# LED-controller-3.net
KiCad netlist of a schematic drawn in EAGLE
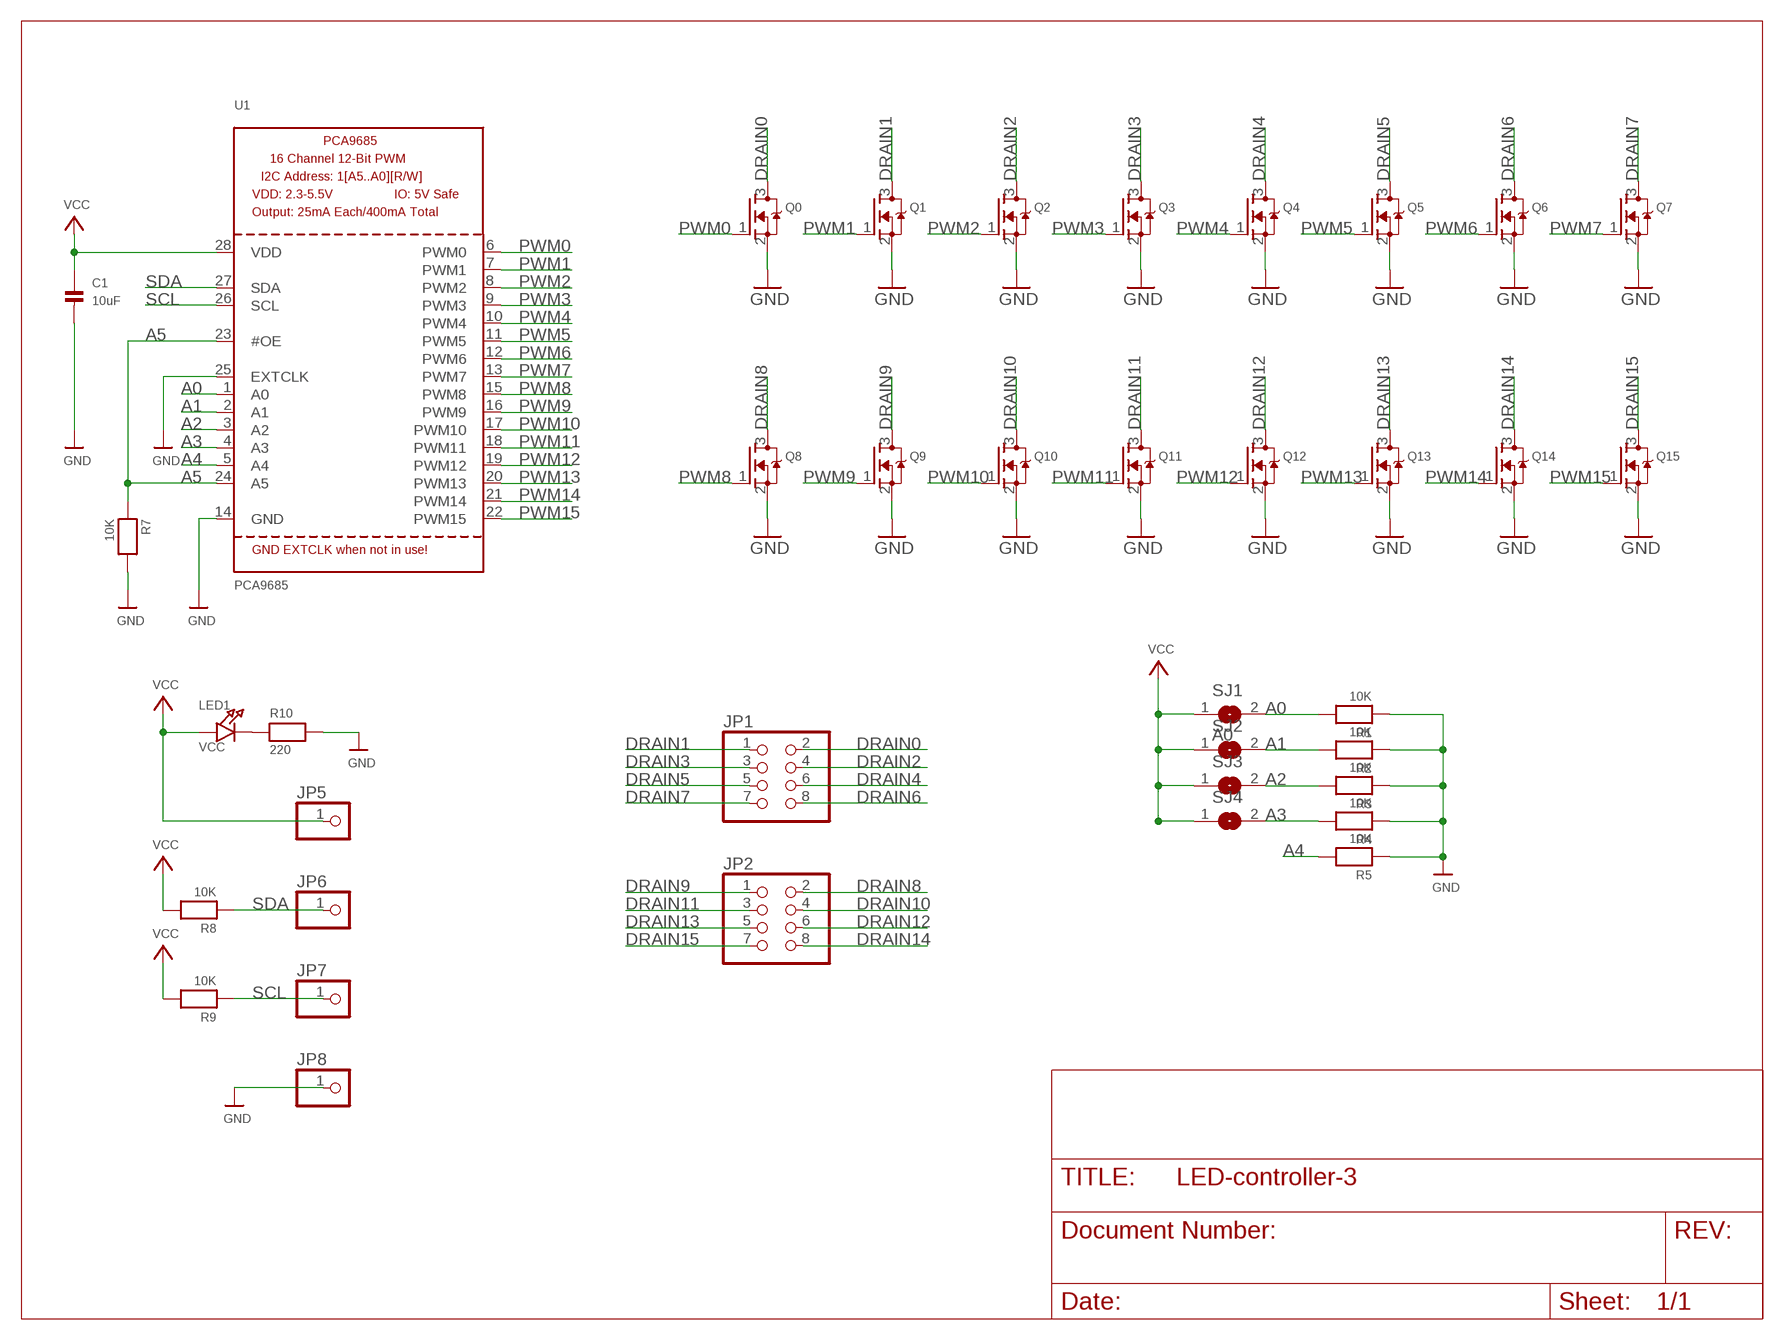
[diagram p0: schematic, sheet 1]

(export (version "E")
  (design (tool "Eeschema 10.0.6"))
  (components
    (comp (ref "C1")
      (value "10uF")
      (footprint "eagle-import:0805")
      (libsource (lib "eagle-import") (part "CAP_CERAMIC0805"))
    )
    (comp (ref "JP1")
      (value "PINHD-2X4")
      (footprint "eagle-import:2X04")
      (libsource (lib "eagle-import") (part "PINHD-2X4"))
    )
    (comp (ref "JP2")
      (value "PINHD-2X4")
      (footprint "eagle-import:2X04")
      (libsource (lib "eagle-import") (part "PINHD-2X4"))
    )
    (comp (ref "JP5")
      (value "PINHD-1X1CB")
      (footprint "eagle-import:1X01-CLEANBIG")
      (libsource (lib "eagle-import") (part "PINHD-1X1CB"))
    )
    (comp (ref "JP6")
      (value "PINHD-1X1CB")
      (footprint "eagle-import:1X01-CLEANBIG")
      (libsource (lib "eagle-import") (part "PINHD-1X1CB"))
    )
    (comp (ref "JP7")
      (value "PINHD-1X1CB")
      (footprint "eagle-import:1X01-CLEANBIG")
      (libsource (lib "eagle-import") (part "PINHD-1X1CB"))
    )
    (comp (ref "JP8")
      (value "PINHD-1X1CB")
      (footprint "eagle-import:1X01-CLEANBIG")
      (libsource (lib "eagle-import") (part "PINHD-1X1CB"))
    )
    (comp (ref "LED1")
      (value "VCC")
      (footprint "eagle-import:CHIPLED_0805")
      (libsource (lib "eagle-import") (part "LED0805"))
    )
    (comp (ref "Q0")
      (value "MOSFET-NREFLOW")
      (footprint "eagle-import:SOT23")
      (libsource (lib "eagle-import") (part "MOSFET-NREFLOW"))
    )
    (comp (ref "Q1")
      (value "MOSFET-NREFLOW")
      (footprint "eagle-import:SOT23")
      (libsource (lib "eagle-import") (part "MOSFET-NREFLOW"))
    )
    (comp (ref "Q2")
      (value "MOSFET-NREFLOW")
      (footprint "eagle-import:SOT23")
      (libsource (lib "eagle-import") (part "MOSFET-NREFLOW"))
    )
    (comp (ref "Q3")
      (value "MOSFET-NREFLOW")
      (footprint "eagle-import:SOT23")
      (libsource (lib "eagle-import") (part "MOSFET-NREFLOW"))
    )
    (comp (ref "Q4")
      (value "MOSFET-NREFLOW")
      (footprint "eagle-import:SOT23")
      (libsource (lib "eagle-import") (part "MOSFET-NREFLOW"))
    )
    (comp (ref "Q5")
      (value "MOSFET-NREFLOW")
      (footprint "eagle-import:SOT23")
      (libsource (lib "eagle-import") (part "MOSFET-NREFLOW"))
    )
    (comp (ref "Q6")
      (value "MOSFET-NREFLOW")
      (footprint "eagle-import:SOT23")
      (libsource (lib "eagle-import") (part "MOSFET-NREFLOW"))
    )
    (comp (ref "Q7")
      (value "MOSFET-NREFLOW")
      (footprint "eagle-import:SOT23")
      (libsource (lib "eagle-import") (part "MOSFET-NREFLOW"))
    )
    (comp (ref "Q8")
      (value "MOSFET-NREFLOW")
      (footprint "eagle-import:SOT23")
      (libsource (lib "eagle-import") (part "MOSFET-NREFLOW"))
    )
    (comp (ref "Q9")
      (value "MOSFET-NREFLOW")
      (footprint "eagle-import:SOT23")
      (libsource (lib "eagle-import") (part "MOSFET-NREFLOW"))
    )
    (comp (ref "Q10")
      (value "MOSFET-NREFLOW")
      (footprint "eagle-import:SOT23")
      (libsource (lib "eagle-import") (part "MOSFET-NREFLOW"))
    )
    (comp (ref "Q11")
      (value "MOSFET-NREFLOW")
      (footprint "eagle-import:SOT23")
      (libsource (lib "eagle-import") (part "MOSFET-NREFLOW"))
    )
    (comp (ref "Q12")
      (value "MOSFET-NREFLOW")
      (footprint "eagle-import:SOT23")
      (libsource (lib "eagle-import") (part "MOSFET-NREFLOW"))
    )
    (comp (ref "Q13")
      (value "MOSFET-NREFLOW")
      (footprint "eagle-import:SOT23")
      (libsource (lib "eagle-import") (part "MOSFET-NREFLOW"))
    )
    (comp (ref "Q14")
      (value "MOSFET-NREFLOW")
      (footprint "eagle-import:SOT23")
      (libsource (lib "eagle-import") (part "MOSFET-NREFLOW"))
    )
    (comp (ref "Q15")
      (value "MOSFET-NREFLOW")
      (footprint "eagle-import:SOT23")
      (libsource (lib "eagle-import") (part "MOSFET-NREFLOW"))
    )
    (comp (ref "R1")
      (value "10K")
      (footprint "eagle-import:0603")
      (libsource (lib "eagle-import") (part "RESISTOR0603"))
    )
    (comp (ref "R2")
      (value "10K")
      (footprint "eagle-import:0603")
      (libsource (lib "eagle-import") (part "RESISTOR0603"))
    )
    (comp (ref "R3")
      (value "10K")
      (footprint "eagle-import:0603")
      (libsource (lib "eagle-import") (part "RESISTOR0603"))
    )
    (comp (ref "R4")
      (value "10K")
      (footprint "eagle-import:0603")
      (libsource (lib "eagle-import") (part "RESISTOR0603"))
    )
    (comp (ref "R5")
      (value "10K")
      (footprint "eagle-import:0603")
      (libsource (lib "eagle-import") (part "RESISTOR0603"))
    )
    (comp (ref "R7")
      (value "10K")
      (footprint "eagle-import:0603")
      (libsource (lib "eagle-import") (part "RESISTOR0603"))
    )
    (comp (ref "R8")
      (value "10K")
      (footprint "eagle-import:0603")
      (libsource (lib "eagle-import") (part "RESISTOR0603"))
    )
    (comp (ref "R9")
      (value "10K")
      (footprint "eagle-import:0603")
      (libsource (lib "eagle-import") (part "RESISTOR0603"))
    )
    (comp (ref "R10")
      (value "220")
      (footprint "eagle-import:0603")
      (libsource (lib "eagle-import") (part "RESISTOR0603"))
    )
    (comp (ref "SJ1") (value "A0") (footprint "eagle-import:SJ") (libsource (lib "eagle-import") (part "SJ")))
    (comp (ref "SJ2") (value "SJ") (footprint "eagle-import:SJ") (libsource (lib "eagle-import") (part "SJ")))
    (comp (ref "SJ3") (value "SJ") (footprint "eagle-import:SJ") (libsource (lib "eagle-import") (part "SJ")))
    (comp (ref "SJ4") (value "SJ") (footprint "eagle-import:SJ") (libsource (lib "eagle-import") (part "SJ")))
    (comp (ref "U1")
      (value "PCA9685")
      (footprint "eagle-import:TSSOP28")
      (libsource (lib "eagle-import") (part "PCA9685"))
    )
  )
  (nets
    (net (code "1") (name "/A0") (class "Default")
      (node (ref "R1") (pin "2") (pinfunction "2_2") (pintype "passive"))
      (node (ref "SJ1") (pin "2") (pinfunction "2_2") (pintype "passive"))
      (node (ref "U1") (pin "1") (pinfunction "A0_1") (pintype "bidirectional"))
    )
    (net (code "2") (name "/A1") (class "Default")
      (node (ref "R2") (pin "2") (pinfunction "2_2") (pintype "passive"))
      (node (ref "SJ2") (pin "2") (pinfunction "2_2") (pintype "passive"))
      (node (ref "U1") (pin "2") (pinfunction "A1_2") (pintype "bidirectional"))
    )
    (net (code "3") (name "/A2") (class "Default")
      (node (ref "R3") (pin "2") (pinfunction "2_2") (pintype "passive"))
      (node (ref "SJ3") (pin "2") (pinfunction "2_2") (pintype "passive"))
      (node (ref "U1") (pin "3") (pinfunction "A2_3") (pintype "bidirectional"))
    )
    (net (code "4") (name "/A3") (class "Default")
      (node (ref "R4") (pin "2") (pinfunction "2_2") (pintype "passive"))
      (node (ref "SJ4") (pin "2") (pinfunction "2_2") (pintype "passive"))
      (node (ref "U1") (pin "4") (pinfunction "A3_4") (pintype "bidirectional"))
    )
    (net (code "5") (name "/A4") (class "Default")
      (node (ref "R5") (pin "2") (pinfunction "2_2") (pintype "passive"))
      (node (ref "U1") (pin "5") (pinfunction "A4_5") (pintype "bidirectional"))
    )
    (net (code "6") (name "/A5") (class "Default")
      (node (ref "R7") (pin "1") (pinfunction "1_1") (pintype "passive"))
      (node (ref "U1") (pin "23") (pinfunction "#OE_23") (pintype "input"))
      (node (ref "U1") (pin "24") (pinfunction "A5_24") (pintype "bidirectional"))
    )
    (net (code "7") (name "/DRAIN0") (class "Default")
      (node (ref "JP1") (pin "2") (pinfunction "2_2") (pintype "passive"))
      (node (ref "Q0") (pin "3") (pinfunction "D_3") (pintype "bidirectional"))
    )
    (net (code "8") (name "/DRAIN1") (class "Default")
      (node (ref "JP1") (pin "1") (pinfunction "1_1") (pintype "passive"))
      (node (ref "Q1") (pin "3") (pinfunction "D_3") (pintype "bidirectional"))
    )
    (net (code "9") (name "/DRAIN2") (class "Default")
      (node (ref "JP1") (pin "4") (pinfunction "4_4") (pintype "passive"))
      (node (ref "Q2") (pin "3") (pinfunction "D_3") (pintype "bidirectional"))
    )
    (net (code "10") (name "/DRAIN3") (class "Default")
      (node (ref "JP1") (pin "3") (pinfunction "3_3") (pintype "passive"))
      (node (ref "Q3") (pin "3") (pinfunction "D_3") (pintype "bidirectional"))
    )
    (net (code "11") (name "/DRAIN4") (class "Default")
      (node (ref "JP1") (pin "6") (pinfunction "6_6") (pintype "passive"))
      (node (ref "Q4") (pin "3") (pinfunction "D_3") (pintype "bidirectional"))
    )
    (net (code "12") (name "/DRAIN5") (class "Default")
      (node (ref "JP1") (pin "5") (pinfunction "5_5") (pintype "passive"))
      (node (ref "Q5") (pin "3") (pinfunction "D_3") (pintype "bidirectional"))
    )
    (net (code "13") (name "/DRAIN6") (class "Default")
      (node (ref "JP1") (pin "8") (pinfunction "8_8") (pintype "passive"))
      (node (ref "Q6") (pin "3") (pinfunction "D_3") (pintype "bidirectional"))
    )
    (net (code "14") (name "/DRAIN7") (class "Default")
      (node (ref "JP1") (pin "7") (pinfunction "7_7") (pintype "passive"))
      (node (ref "Q7") (pin "3") (pinfunction "D_3") (pintype "bidirectional"))
    )
    (net (code "15") (name "/DRAIN8") (class "Default")
      (node (ref "JP2") (pin "2") (pinfunction "2_2") (pintype "passive"))
      (node (ref "Q8") (pin "3") (pinfunction "D_3") (pintype "bidirectional"))
    )
    (net (code "16") (name "/DRAIN9") (class "Default")
      (node (ref "JP2") (pin "1") (pinfunction "1_1") (pintype "passive"))
      (node (ref "Q9") (pin "3") (pinfunction "D_3") (pintype "bidirectional"))
    )
    (net (code "17") (name "/DRAIN10") (class "Default")
      (node (ref "JP2") (pin "4") (pinfunction "4_4") (pintype "passive"))
      (node (ref "Q10") (pin "3") (pinfunction "D_3") (pintype "bidirectional"))
    )
    (net (code "18") (name "/DRAIN11") (class "Default")
      (node (ref "JP2") (pin "3") (pinfunction "3_3") (pintype "passive"))
      (node (ref "Q11") (pin "3") (pinfunction "D_3") (pintype "bidirectional"))
    )
    (net (code "19") (name "/DRAIN12") (class "Default")
      (node (ref "JP2") (pin "6") (pinfunction "6_6") (pintype "passive"))
      (node (ref "Q12") (pin "3") (pinfunction "D_3") (pintype "bidirectional"))
    )
    (net (code "20") (name "/DRAIN13") (class "Default")
      (node (ref "JP2") (pin "5") (pinfunction "5_5") (pintype "passive"))
      (node (ref "Q13") (pin "3") (pinfunction "D_3") (pintype "bidirectional"))
    )
    (net (code "21") (name "/DRAIN14") (class "Default")
      (node (ref "JP2") (pin "8") (pinfunction "8_8") (pintype "passive"))
      (node (ref "Q14") (pin "3") (pinfunction "D_3") (pintype "bidirectional"))
    )
    (net (code "22") (name "/DRAIN15") (class "Default")
      (node (ref "JP2") (pin "7") (pinfunction "7_7") (pintype "passive"))
      (node (ref "Q15") (pin "3") (pinfunction "D_3") (pintype "bidirectional"))
    )
    (net (code "23") (name "/PWM0") (class "Default")
      (node (ref "Q0") (pin "1") (pinfunction "G_1") (pintype "bidirectional"))
      (node (ref "U1") (pin "6") (pinfunction "PWM0_6") (pintype "output"))
    )
    (net (code "24") (name "/PWM1") (class "Default")
      (node (ref "Q1") (pin "1") (pinfunction "G_1") (pintype "bidirectional"))
      (node (ref "U1") (pin "7") (pinfunction "PWM1_7") (pintype "output"))
    )
    (net (code "25") (name "/PWM2") (class "Default")
      (node (ref "Q2") (pin "1") (pinfunction "G_1") (pintype "bidirectional"))
      (node (ref "U1") (pin "8") (pinfunction "PWM2_8") (pintype "output"))
    )
    (net (code "26") (name "/PWM3") (class "Default")
      (node (ref "Q3") (pin "1") (pinfunction "G_1") (pintype "bidirectional"))
      (node (ref "U1") (pin "9") (pinfunction "PWM3_9") (pintype "output"))
    )
    (net (code "27") (name "/PWM4") (class "Default")
      (node (ref "Q4") (pin "1") (pinfunction "G_1") (pintype "bidirectional"))
      (node (ref "U1") (pin "10") (pinfunction "PWM4_10") (pintype "output"))
    )
    (net (code "28") (name "/PWM5") (class "Default")
      (node (ref "Q5") (pin "1") (pinfunction "G_1") (pintype "bidirectional"))
      (node (ref "U1") (pin "11") (pinfunction "PWM5_11") (pintype "output"))
    )
    (net (code "29") (name "/PWM6") (class "Default")
      (node (ref "Q6") (pin "1") (pinfunction "G_1") (pintype "bidirectional"))
      (node (ref "U1") (pin "12") (pinfunction "PWM6_12") (pintype "output"))
    )
    (net (code "30") (name "/PWM7") (class "Default")
      (node (ref "Q7") (pin "1") (pinfunction "G_1") (pintype "bidirectional"))
      (node (ref "U1") (pin "13") (pinfunction "PWM7_13") (pintype "output"))
    )
    (net (code "31") (name "/PWM8") (class "Default")
      (node (ref "Q8") (pin "1") (pinfunction "G_1") (pintype "bidirectional"))
      (node (ref "U1") (pin "15") (pinfunction "PWM8_15") (pintype "output"))
    )
    (net (code "32") (name "/PWM9") (class "Default")
      (node (ref "Q9") (pin "1") (pinfunction "G_1") (pintype "bidirectional"))
      (node (ref "U1") (pin "16") (pinfunction "PWM9_16") (pintype "output"))
    )
    (net (code "33") (name "/PWM10") (class "Default")
      (node (ref "Q10") (pin "1") (pinfunction "G_1") (pintype "bidirectional"))
      (node (ref "U1") (pin "17") (pinfunction "PWM10_17") (pintype "output"))
    )
    (net (code "34") (name "/PWM11") (class "Default")
      (node (ref "Q11") (pin "1") (pinfunction "G_1") (pintype "bidirectional"))
      (node (ref "U1") (pin "18") (pinfunction "PWM11_18") (pintype "output"))
    )
    (net (code "35") (name "/PWM12") (class "Default")
      (node (ref "Q12") (pin "1") (pinfunction "G_1") (pintype "bidirectional"))
      (node (ref "U1") (pin "19") (pinfunction "PWM12_19") (pintype "output"))
    )
    (net (code "36") (name "/PWM13") (class "Default")
      (node (ref "Q13") (pin "1") (pinfunction "G_1") (pintype "bidirectional"))
      (node (ref "U1") (pin "20") (pinfunction "PWM13_20") (pintype "output"))
    )
    (net (code "37") (name "/PWM14") (class "Default")
      (node (ref "Q14") (pin "1") (pinfunction "G_1") (pintype "bidirectional"))
      (node (ref "U1") (pin "21") (pinfunction "PWM14_21") (pintype "output"))
    )
    (net (code "38") (name "/PWM15") (class "Default")
      (node (ref "Q15") (pin "1") (pinfunction "G_1") (pintype "bidirectional"))
      (node (ref "U1") (pin "22") (pinfunction "PWM15_22") (pintype "output"))
    )
    (net (code "39") (name "/SCL") (class "Default")
      (node (ref "JP7") (pin "1") (pinfunction "1_1") (pintype "passive"))
      (node (ref "R9") (pin "1") (pinfunction "1_1") (pintype "passive"))
      (node (ref "U1") (pin "26") (pinfunction "SCL_26") (pintype "bidirectional"))
    )
    (net (code "40") (name "/SDA") (class "Default")
      (node (ref "JP6") (pin "1") (pinfunction "1_1") (pintype "passive"))
      (node (ref "R8") (pin "1") (pinfunction "1_1") (pintype "passive"))
      (node (ref "U1") (pin "27") (pinfunction "SDA_27") (pintype "bidirectional"))
    )
    (net (code "41") (name "GND") (class "Default")
      (node (ref "C1") (pin "2") (pinfunction "P$2_2") (pintype "passive"))
      (node (ref "JP8") (pin "1") (pinfunction "1_1") (pintype "passive"))
      (node (ref "Q0") (pin "2") (pinfunction "S_2") (pintype "bidirectional"))
      (node (ref "Q1") (pin "2") (pinfunction "S_2") (pintype "bidirectional"))
      (node (ref "Q10") (pin "2") (pinfunction "S_2") (pintype "bidirectional"))
      (node (ref "Q11") (pin "2") (pinfunction "S_2") (pintype "bidirectional"))
      (node (ref "Q12") (pin "2") (pinfunction "S_2") (pintype "bidirectional"))
      (node (ref "Q13") (pin "2") (pinfunction "S_2") (pintype "bidirectional"))
      (node (ref "Q14") (pin "2") (pinfunction "S_2") (pintype "bidirectional"))
      (node (ref "Q15") (pin "2") (pinfunction "S_2") (pintype "bidirectional"))
      (node (ref "Q2") (pin "2") (pinfunction "S_2") (pintype "bidirectional"))
      (node (ref "Q3") (pin "2") (pinfunction "S_2") (pintype "bidirectional"))
      (node (ref "Q4") (pin "2") (pinfunction "S_2") (pintype "bidirectional"))
      (node (ref "Q5") (pin "2") (pinfunction "S_2") (pintype "bidirectional"))
      (node (ref "Q6") (pin "2") (pinfunction "S_2") (pintype "bidirectional"))
      (node (ref "Q7") (pin "2") (pinfunction "S_2") (pintype "bidirectional"))
      (node (ref "Q8") (pin "2") (pinfunction "S_2") (pintype "bidirectional"))
      (node (ref "Q9") (pin "2") (pinfunction "S_2") (pintype "bidirectional"))
      (node (ref "R1") (pin "1") (pinfunction "1_1") (pintype "passive"))
      (node (ref "R10") (pin "2") (pinfunction "2_2") (pintype "passive"))
      (node (ref "R2") (pin "1") (pinfunction "1_1") (pintype "passive"))
      (node (ref "R3") (pin "1") (pinfunction "1_1") (pintype "passive"))
      (node (ref "R4") (pin "1") (pinfunction "1_1") (pintype "passive"))
      (node (ref "R5") (pin "1") (pinfunction "1_1") (pintype "passive"))
      (node (ref "R7") (pin "2") (pinfunction "2_2") (pintype "passive"))
      (node (ref "U1") (pin "14") (pinfunction "GND_14") (pintype "power_in"))
      (node (ref "U1") (pin "25") (pinfunction "EXTCLK_25") (pintype "input"))
    )
    (net (code "42") (name "Net-(LED1-PadC)") (class "Default")
      (node (ref "LED1") (pin "C") (pinfunction "C_C") (pintype "passive"))
      (node (ref "R10") (pin "1") (pinfunction "1_1") (pintype "passive"))
    )
    (net (code "43") (name "VCC") (class "Default")
      (node (ref "C1") (pin "1") (pinfunction "P$1_1") (pintype "passive"))
      (node (ref "JP5") (pin "1") (pinfunction "1_1") (pintype "passive"))
      (node (ref "LED1") (pin "A") (pinfunction "A_A") (pintype "passive"))
      (node (ref "R8") (pin "2") (pinfunction "2_2") (pintype "passive"))
      (node (ref "R9") (pin "2") (pinfunction "2_2") (pintype "passive"))
      (node (ref "SJ1") (pin "1") (pinfunction "1_1") (pintype "passive"))
      (node (ref "SJ2") (pin "1") (pinfunction "1_1") (pintype "passive"))
      (node (ref "SJ3") (pin "1") (pinfunction "1_1") (pintype "passive"))
      (node (ref "SJ4") (pin "1") (pinfunction "1_1") (pintype "passive"))
      (node (ref "U1") (pin "28") (pinfunction "VDD_28") (pintype "power_in"))
    )
  )
)
